# UltiMem64_Color_CPLD.net
KiCad netlist of a schematic drawn in EAGLE
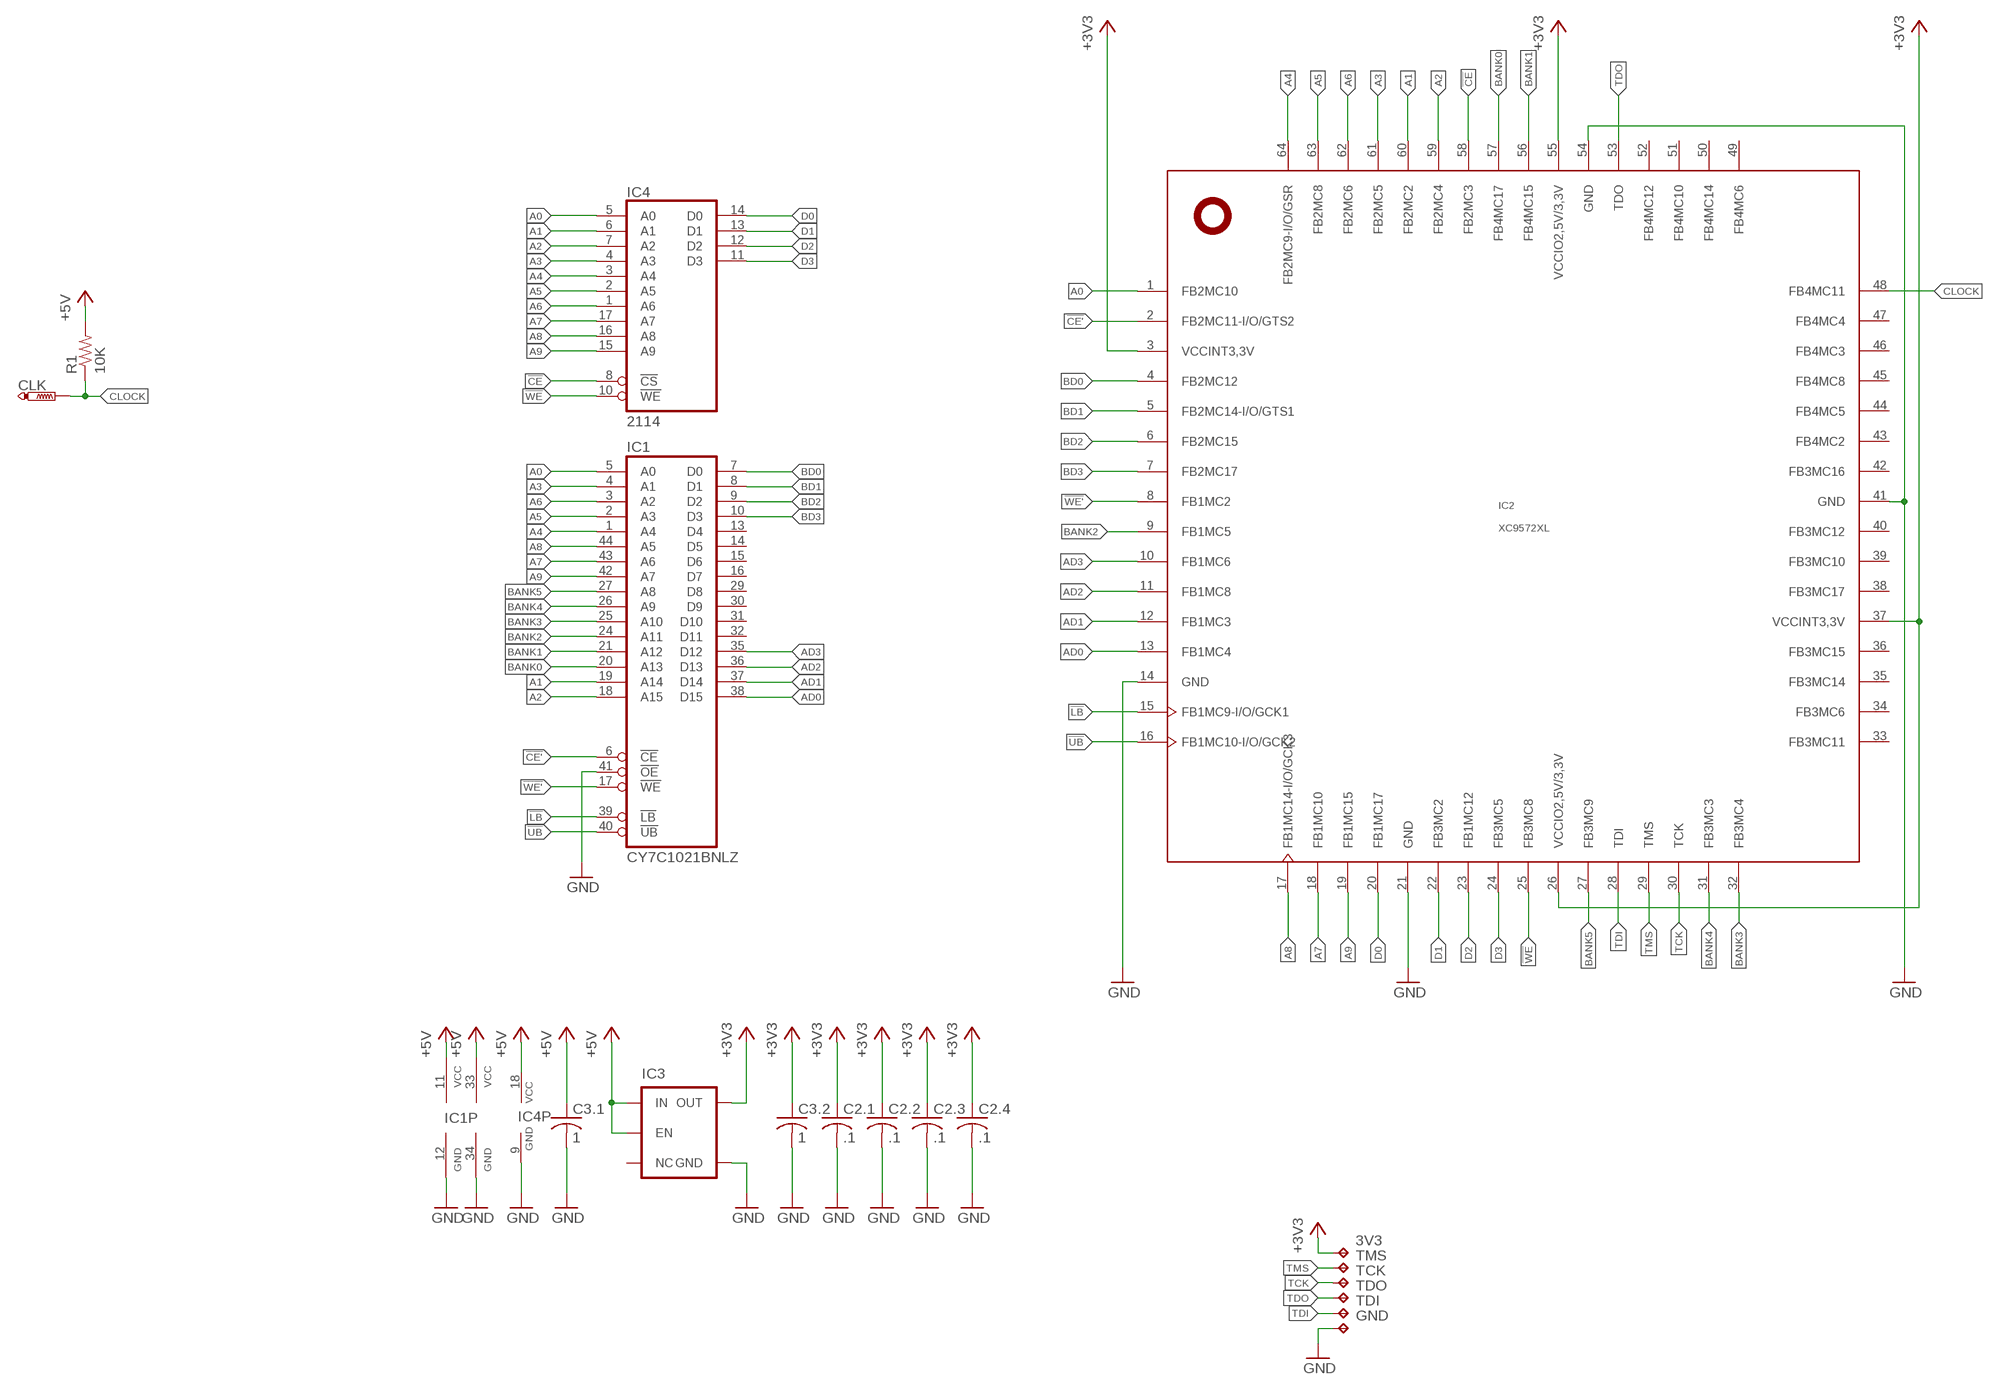
[diagram p0: schematic, sheet 1]

(export (version "E")
  (design (tool "Eeschema 10.0.6"))
  (components
    (comp (ref "3V3")
      (value "TPTP09R")
      (footprint "eagle-import:TP09R")
      (libsource (lib "eagle-import") (part "TPTP09R"))
    )
    (comp (ref "C2.1")
      (value ".1")
      (footprint "eagle-import:C0402")
      (libsource (lib "eagle-import") (part "C-USC0402"))
    )
    (comp (ref "C2.2")
      (value ".1")
      (footprint "eagle-import:C0402")
      (libsource (lib "eagle-import") (part "C-USC0402"))
    )
    (comp (ref "C2.3")
      (value ".1")
      (footprint "eagle-import:C0402")
      (libsource (lib "eagle-import") (part "C-USC0402"))
    )
    (comp (ref "C2.4")
      (value ".1")
      (footprint "eagle-import:C0402")
      (libsource (lib "eagle-import") (part "C-USC0402"))
    )
    (comp (ref "C3.1")
      (value "1")
      (footprint "eagle-import:C0402")
      (libsource (lib "eagle-import") (part "C-USC0402"))
    )
    (comp (ref "C3.2")
      (value "1")
      (footprint "eagle-import:C0402")
      (libsource (lib "eagle-import") (part "C-USC0402"))
    )
    (comp (ref "CLK")
      (value "PTR1PAD1-13")
      (footprint "eagle-import:P1-13")
      (libsource (lib "eagle-import") (part "PTR1PAD1-13"))
    )
    (comp (ref "GND")
      (value "TPTP09R")
      (footprint "eagle-import:TP09R")
      (libsource (lib "eagle-import") (part "TPTP09R"))
    )
    (comp (ref "IC1")
      (value "CY7C1021BNLZ")
      (footprint "eagle-import:TSOP44-II")
      (libsource (lib "eagle-import") (part "CY7C1021BNLZ"))
    )
    (comp (ref "IC2")
      (value "XC9572XL")
      (footprint "eagle-import:VQFP64")
      (libsource (lib "eagle-import") (part "XC9572XLVQG64"))
    )
    (comp (ref "IC3")
      (value "V_REG_TPS76433SOT23-5")
      (footprint "eagle-import:SOT23-5")
      (libsource (lib "eagle-import") (part "V_REG_TPS76433SOT23-5"))
    )
    (comp (ref "IC4")
      (value "2114")
      (footprint "eagle-import:DIL18-SMD-REVERSE")
      (libsource (lib "eagle-import") (part "2114-S"))
    )
    (comp (ref "R1")
      (value "10K")
      (footprint "eagle-import:R0402")
      (libsource (lib "eagle-import") (part "R-US_R0402"))
    )
    (comp (ref "TCK")
      (value "TPTP09R")
      (footprint "eagle-import:TP09R")
      (libsource (lib "eagle-import") (part "TPTP09R"))
    )
    (comp (ref "TDI")
      (value "TPTP09R")
      (footprint "eagle-import:TP09R")
      (libsource (lib "eagle-import") (part "TPTP09R"))
    )
    (comp (ref "TDO")
      (value "TPTP09R")
      (footprint "eagle-import:TP09R")
      (libsource (lib "eagle-import") (part "TPTP09R"))
    )
    (comp (ref "TMS")
      (value "TPTP09R")
      (footprint "eagle-import:TP09R")
      (libsource (lib "eagle-import") (part "TPTP09R"))
    )
  )
  (nets
    (net (code "1") (name "+3V3") (class "Default")
      (node (ref "3V3") (pin "TP") (pinfunction "TP_TP") (pintype "input"))
      (node (ref "C2.1") (pin "1") (pinfunction "1_1") (pintype "passive"))
      (node (ref "C2.2") (pin "1") (pinfunction "1_1") (pintype "passive"))
      (node (ref "C2.3") (pin "1") (pinfunction "1_1") (pintype "passive"))
      (node (ref "C2.4") (pin "1") (pinfunction "1_1") (pintype "passive"))
      (node (ref "C3.2") (pin "1") (pinfunction "1_1") (pintype "passive"))
      (node (ref "IC2") (pin "26") (pinfunction "VCCIO2,5V/3,3V_26") (pintype "power_in"))
      (node (ref "IC2") (pin "3") (pinfunction "VCCINT3,3V_3") (pintype "power_in"))
      (node (ref "IC2") (pin "37") (pinfunction "VCCINT3,3V_37") (pintype "power_in"))
      (node (ref "IC2") (pin "55") (pinfunction "VCCIO2,5V/3,3V_55") (pintype "power_in"))
      (node (ref "IC3") (pin "5") (pinfunction "OUT_5") (pintype "passive"))
    )
    (net (code "2") (name "+5V") (class "Default")
      (node (ref "C3.1") (pin "1") (pinfunction "1_1") (pintype "passive"))
      (node (ref "IC1") (pin "11") (pinfunction "VCC_11") (pintype "power_in"))
      (node (ref "IC1") (pin "33") (pinfunction "VCC_33") (pintype "power_in"))
      (node (ref "IC3") (pin "1") (pinfunction "IN_1") (pintype "input"))
      (node (ref "IC3") (pin "3") (pinfunction "EN_3") (pintype "input"))
      (node (ref "IC4") (pin "18") (pinfunction "VCC_18") (pintype "power_in"))
      (node (ref "R1") (pin "2") (pinfunction "2_2") (pintype "passive"))
    )
    (net (code "3") (name "/~{CE'}") (class "Default")
      (node (ref "IC1") (pin "6") (pinfunction "~{CE}_6") (pintype "input"))
      (node (ref "IC2") (pin "2") (pinfunction "FB2MC11-I/O/GTS2_2") (pintype "bidirectional"))
    )
    (net (code "4") (name "/~{CE}") (class "Default")
      (node (ref "IC2") (pin "58") (pinfunction "FB2MC3_58") (pintype "bidirectional"))
      (node (ref "IC4") (pin "8") (pinfunction "~{CS}_8") (pintype "input"))
    )
    (net (code "5") (name "/~{LB}") (class "Default")
      (node (ref "IC1") (pin "39") (pinfunction "~{LB}_39") (pintype "input"))
      (node (ref "IC2") (pin "15") (pinfunction "FB1MC9-I/O/GCK1_15") (pintype "bidirectional"))
    )
    (net (code "6") (name "/~{UB}") (class "Default")
      (node (ref "IC1") (pin "40") (pinfunction "~{UB}_40") (pintype "input"))
      (node (ref "IC2") (pin "16") (pinfunction "FB1MC10-I/O/GCK2_16") (pintype "bidirectional"))
    )
    (net (code "7") (name "/~{WE'}") (class "Default")
      (node (ref "IC1") (pin "17") (pinfunction "~{WE}_17") (pintype "input"))
      (node (ref "IC2") (pin "8") (pinfunction "FB1MC2_8") (pintype "bidirectional"))
    )
    (net (code "8") (name "/~{WE}") (class "Default")
      (node (ref "IC2") (pin "25") (pinfunction "FB3MC8_25") (pintype "bidirectional"))
      (node (ref "IC4") (pin "10") (pinfunction "~{WE}_10") (pintype "input"))
    )
    (net (code "9") (name "A0") (class "Default")
      (node (ref "IC1") (pin "5") (pinfunction "A0_5") (pintype "input"))
      (node (ref "IC2") (pin "1") (pinfunction "FB2MC10_1") (pintype "bidirectional"))
      (node (ref "IC4") (pin "5") (pinfunction "A0_5") (pintype "input"))
    )
    (net (code "10") (name "A1") (class "Default")
      (node (ref "IC1") (pin "19") (pinfunction "A14_19") (pintype "input"))
      (node (ref "IC2") (pin "60") (pinfunction "FB2MC2_60") (pintype "bidirectional"))
      (node (ref "IC4") (pin "6") (pinfunction "A1_6") (pintype "input"))
    )
    (net (code "11") (name "A2") (class "Default")
      (node (ref "IC1") (pin "18") (pinfunction "A15_18") (pintype "input"))
      (node (ref "IC2") (pin "59") (pinfunction "FB2MC4_59") (pintype "bidirectional"))
      (node (ref "IC4") (pin "7") (pinfunction "A2_7") (pintype "input"))
    )
    (net (code "12") (name "A3") (class "Default")
      (node (ref "IC1") (pin "4") (pinfunction "A1_4") (pintype "input"))
      (node (ref "IC2") (pin "61") (pinfunction "FB2MC5_61") (pintype "bidirectional"))
      (node (ref "IC4") (pin "4") (pinfunction "A3_4") (pintype "input"))
    )
    (net (code "13") (name "A4") (class "Default")
      (node (ref "IC1") (pin "1") (pinfunction "A4_1") (pintype "input"))
      (node (ref "IC2") (pin "64") (pinfunction "FB2MC9-I/O/GSR_64") (pintype "bidirectional"))
      (node (ref "IC4") (pin "3") (pinfunction "A4_3") (pintype "input"))
    )
    (net (code "14") (name "A5") (class "Default")
      (node (ref "IC1") (pin "2") (pinfunction "A3_2") (pintype "input"))
      (node (ref "IC2") (pin "63") (pinfunction "FB2MC8_63") (pintype "bidirectional"))
      (node (ref "IC4") (pin "2") (pinfunction "A5_2") (pintype "input"))
    )
    (net (code "15") (name "A6") (class "Default")
      (node (ref "IC1") (pin "3") (pinfunction "A2_3") (pintype "input"))
      (node (ref "IC2") (pin "62") (pinfunction "FB2MC6_62") (pintype "bidirectional"))
      (node (ref "IC4") (pin "1") (pinfunction "A6_1") (pintype "input"))
    )
    (net (code "16") (name "A7") (class "Default")
      (node (ref "IC1") (pin "43") (pinfunction "A6_43") (pintype "input"))
      (node (ref "IC2") (pin "18") (pinfunction "FB1MC10_18") (pintype "bidirectional"))
      (node (ref "IC4") (pin "17") (pinfunction "A7_17") (pintype "input"))
    )
    (net (code "17") (name "A8") (class "Default")
      (node (ref "IC1") (pin "44") (pinfunction "A5_44") (pintype "input"))
      (node (ref "IC2") (pin "17") (pinfunction "FB1MC14-I/O/GCK3_17") (pintype "bidirectional"))
      (node (ref "IC4") (pin "16") (pinfunction "A8_16") (pintype "input"))
    )
    (net (code "18") (name "A9") (class "Default")
      (node (ref "IC1") (pin "42") (pinfunction "A7_42") (pintype "input"))
      (node (ref "IC2") (pin "19") (pinfunction "FB1MC15_19") (pintype "bidirectional"))
      (node (ref "IC4") (pin "15") (pinfunction "A9_15") (pintype "input"))
    )
    (net (code "19") (name "AD0") (class "Default")
      (node (ref "IC1") (pin "38") (pinfunction "D15_38") (pintype "bidirectional"))
      (node (ref "IC2") (pin "13") (pinfunction "FB1MC4_13") (pintype "bidirectional"))
    )
    (net (code "20") (name "AD1") (class "Default")
      (node (ref "IC1") (pin "37") (pinfunction "D14_37") (pintype "bidirectional"))
      (node (ref "IC2") (pin "12") (pinfunction "FB1MC3_12") (pintype "bidirectional"))
    )
    (net (code "21") (name "AD2") (class "Default")
      (node (ref "IC1") (pin "36") (pinfunction "D13_36") (pintype "bidirectional"))
      (node (ref "IC2") (pin "11") (pinfunction "FB1MC8_11") (pintype "bidirectional"))
    )
    (net (code "22") (name "AD3") (class "Default")
      (node (ref "IC1") (pin "35") (pinfunction "D12_35") (pintype "bidirectional"))
      (node (ref "IC2") (pin "10") (pinfunction "FB1MC6_10") (pintype "bidirectional"))
    )
    (net (code "23") (name "BANK0") (class "Default")
      (node (ref "IC1") (pin "20") (pinfunction "A13_20") (pintype "input"))
      (node (ref "IC2") (pin "57") (pinfunction "FB4MC17_57") (pintype "bidirectional"))
    )
    (net (code "24") (name "BANK1") (class "Default")
      (node (ref "IC1") (pin "21") (pinfunction "A12_21") (pintype "input"))
      (node (ref "IC2") (pin "56") (pinfunction "FB4MC15_56") (pintype "bidirectional"))
    )
    (net (code "25") (name "BANK2") (class "Default")
      (node (ref "IC1") (pin "24") (pinfunction "A11_24") (pintype "input"))
      (node (ref "IC2") (pin "9") (pinfunction "FB1MC5_9") (pintype "bidirectional"))
    )
    (net (code "26") (name "BANK3") (class "Default")
      (node (ref "IC1") (pin "25") (pinfunction "A10_25") (pintype "input"))
      (node (ref "IC2") (pin "32") (pinfunction "FB3MC4_32") (pintype "bidirectional"))
    )
    (net (code "27") (name "BANK4") (class "Default")
      (node (ref "IC1") (pin "26") (pinfunction "A9_26") (pintype "input"))
      (node (ref "IC2") (pin "31") (pinfunction "FB3MC3_31") (pintype "bidirectional"))
    )
    (net (code "28") (name "BANK5") (class "Default")
      (node (ref "IC1") (pin "27") (pinfunction "A8_27") (pintype "input"))
      (node (ref "IC2") (pin "27") (pinfunction "FB3MC9_27") (pintype "bidirectional"))
    )
    (net (code "29") (name "BD0") (class "Default")
      (node (ref "IC1") (pin "7") (pinfunction "D0_7") (pintype "bidirectional"))
      (node (ref "IC2") (pin "4") (pinfunction "FB2MC12_4") (pintype "bidirectional"))
    )
    (net (code "30") (name "BD1") (class "Default")
      (node (ref "IC1") (pin "8") (pinfunction "D1_8") (pintype "bidirectional"))
      (node (ref "IC2") (pin "5") (pinfunction "FB2MC14-I/O/GTS1_5") (pintype "bidirectional"))
    )
    (net (code "31") (name "BD2") (class "Default")
      (node (ref "IC1") (pin "9") (pinfunction "D2_9") (pintype "bidirectional"))
      (node (ref "IC2") (pin "6") (pinfunction "FB2MC15_6") (pintype "bidirectional"))
    )
    (net (code "32") (name "BD3") (class "Default")
      (node (ref "IC1") (pin "10") (pinfunction "D3_10") (pintype "bidirectional"))
      (node (ref "IC2") (pin "7") (pinfunction "FB2MC17_7") (pintype "bidirectional"))
    )
    (net (code "33") (name "CLOCK") (class "Default")
      (node (ref "CLK") (pin "TP") (pinfunction "TP_TP") (pintype "input"))
      (node (ref "IC2") (pin "48") (pinfunction "FB4MC11_48") (pintype "bidirectional"))
      (node (ref "R1") (pin "1") (pinfunction "1_1") (pintype "passive"))
    )
    (net (code "34") (name "D0") (class "Default")
      (node (ref "IC2") (pin "20") (pinfunction "FB1MC17_20") (pintype "bidirectional"))
      (node (ref "IC4") (pin "14") (pinfunction "D0_14") (pintype "bidirectional"))
    )
    (net (code "35") (name "D1") (class "Default")
      (node (ref "IC2") (pin "22") (pinfunction "FB3MC2_22") (pintype "bidirectional"))
      (node (ref "IC4") (pin "13") (pinfunction "D1_13") (pintype "bidirectional"))
    )
    (net (code "36") (name "D2") (class "Default")
      (node (ref "IC2") (pin "23") (pinfunction "FB1MC12_23") (pintype "bidirectional"))
      (node (ref "IC4") (pin "12") (pinfunction "D2_12") (pintype "bidirectional"))
    )
    (net (code "37") (name "D3") (class "Default")
      (node (ref "IC2") (pin "24") (pinfunction "FB3MC5_24") (pintype "bidirectional"))
      (node (ref "IC4") (pin "11") (pinfunction "D3_11") (pintype "bidirectional"))
    )
    (net (code "38") (name "GND") (class "Default")
      (node (ref "C2.1") (pin "2") (pinfunction "2_2") (pintype "passive"))
      (node (ref "C2.2") (pin "2") (pinfunction "2_2") (pintype "passive"))
      (node (ref "C2.3") (pin "2") (pinfunction "2_2") (pintype "passive"))
      (node (ref "C2.4") (pin "2") (pinfunction "2_2") (pintype "passive"))
      (node (ref "C3.1") (pin "2") (pinfunction "2_2") (pintype "passive"))
      (node (ref "C3.2") (pin "2") (pinfunction "2_2") (pintype "passive"))
      (node (ref "GND") (pin "TP") (pinfunction "TP_TP") (pintype "input"))
      (node (ref "IC1") (pin "12") (pinfunction "GND_12") (pintype "power_in"))
      (node (ref "IC1") (pin "34") (pinfunction "GND_34") (pintype "power_in"))
      (node (ref "IC1") (pin "41") (pinfunction "~{OE}_41") (pintype "input"))
      (node (ref "IC2") (pin "14") (pinfunction "GND_14") (pintype "power_in"))
      (node (ref "IC2") (pin "21") (pinfunction "GND_21") (pintype "power_in"))
      (node (ref "IC2") (pin "41") (pinfunction "GND_41") (pintype "power_in"))
      (node (ref "IC2") (pin "54") (pinfunction "GND_54") (pintype "power_in"))
      (node (ref "IC3") (pin "2") (pinfunction "GND_2") (pintype "input"))
      (node (ref "IC4") (pin "9") (pinfunction "GND_9") (pintype "power_in"))
    )
    (net (code "39") (name "TCK") (class "Default")
      (node (ref "IC2") (pin "30") (pinfunction "TCK_30") (pintype "bidirectional"))
      (node (ref "TCK") (pin "TP") (pinfunction "TP_TP") (pintype "input"))
    )
    (net (code "40") (name "TDI") (class "Default")
      (node (ref "IC2") (pin "28") (pinfunction "TDI_28") (pintype "bidirectional"))
      (node (ref "TDI") (pin "TP") (pinfunction "TP_TP") (pintype "input"))
    )
    (net (code "41") (name "TDO") (class "Default")
      (node (ref "IC2") (pin "53") (pinfunction "TDO_53") (pintype "bidirectional"))
      (node (ref "TDO") (pin "TP") (pinfunction "TP_TP") (pintype "input"))
    )
    (net (code "42") (name "TMS") (class "Default")
      (node (ref "IC2") (pin "29") (pinfunction "TMS_29") (pintype "bidirectional"))
      (node (ref "TMS") (pin "TP") (pinfunction "TP_TP") (pintype "input"))
    )
    (net (code "43") (name "unconnected-(IC1A-D4-Pad13)") (class "Default")
      (node (ref "IC1") (pin "13") (pinfunction "D4_13") (pintype "bidirectional"))
    )
    (net (code "44") (name "unconnected-(IC1A-D5-Pad14)") (class "Default")
      (node (ref "IC1") (pin "14") (pinfunction "D5_14") (pintype "bidirectional"))
    )
    (net (code "45") (name "unconnected-(IC1A-D6-Pad15)") (class "Default")
      (node (ref "IC1") (pin "15") (pinfunction "D6_15") (pintype "bidirectional"))
    )
    (net (code "46") (name "unconnected-(IC1A-D7-Pad16)") (class "Default")
      (node (ref "IC1") (pin "16") (pinfunction "D7_16") (pintype "bidirectional"))
    )
    (net (code "47") (name "unconnected-(IC1A-D8-Pad29)") (class "Default")
      (node (ref "IC1") (pin "29") (pinfunction "D8_29") (pintype "bidirectional"))
    )
    (net (code "48") (name "unconnected-(IC1A-D9-Pad30)") (class "Default")
      (node (ref "IC1") (pin "30") (pinfunction "D9_30") (pintype "bidirectional"))
    )
    (net (code "49") (name "unconnected-(IC1A-D10-Pad31)") (class "Default")
      (node (ref "IC1") (pin "31") (pinfunction "D10_31") (pintype "bidirectional"))
    )
    (net (code "50") (name "unconnected-(IC1A-D11-Pad32)") (class "Default")
      (node (ref "IC1") (pin "32") (pinfunction "D11_32") (pintype "bidirectional"))
    )
    (net (code "51") (name "unconnected-(IC2-FB3MC6-Pad34)") (class "Default")
      (node (ref "IC2") (pin "34") (pinfunction "FB3MC6_34") (pintype "bidirectional"))
    )
    (net (code "52") (name "unconnected-(IC2-FB3MC10-Pad39)") (class "Default")
      (node (ref "IC2") (pin "39") (pinfunction "FB3MC10_39") (pintype "bidirectional"))
    )
    (net (code "53") (name "unconnected-(IC2-FB3MC11-Pad33)") (class "Default")
      (node (ref "IC2") (pin "33") (pinfunction "FB3MC11_33") (pintype "bidirectional"))
    )
    (net (code "54") (name "unconnected-(IC2-FB3MC12-Pad40)") (class "Default")
      (node (ref "IC2") (pin "40") (pinfunction "FB3MC12_40") (pintype "bidirectional"))
    )
    (net (code "55") (name "unconnected-(IC2-FB3MC14-Pad35)") (class "Default")
      (node (ref "IC2") (pin "35") (pinfunction "FB3MC14_35") (pintype "bidirectional"))
    )
    (net (code "56") (name "unconnected-(IC2-FB3MC15-Pad36)") (class "Default")
      (node (ref "IC2") (pin "36") (pinfunction "FB3MC15_36") (pintype "bidirectional"))
    )
    (net (code "57") (name "unconnected-(IC2-FB3MC16-Pad42)") (class "Default")
      (node (ref "IC2") (pin "42") (pinfunction "FB3MC16_42") (pintype "bidirectional"))
    )
    (net (code "58") (name "unconnected-(IC2-FB3MC17-Pad38)") (class "Default")
      (node (ref "IC2") (pin "38") (pinfunction "FB3MC17_38") (pintype "bidirectional"))
    )
    (net (code "59") (name "unconnected-(IC2-FB4MC2-Pad43)") (class "Default")
      (node (ref "IC2") (pin "43") (pinfunction "FB4MC2_43") (pintype "bidirectional"))
    )
    (net (code "60") (name "unconnected-(IC2-FB4MC3-Pad46)") (class "Default")
      (node (ref "IC2") (pin "46") (pinfunction "FB4MC3_46") (pintype "bidirectional"))
    )
    (net (code "61") (name "unconnected-(IC2-FB4MC4-Pad47)") (class "Default")
      (node (ref "IC2") (pin "47") (pinfunction "FB4MC4_47") (pintype "bidirectional"))
    )
    (net (code "62") (name "unconnected-(IC2-FB4MC5-Pad44)") (class "Default")
      (node (ref "IC2") (pin "44") (pinfunction "FB4MC5_44") (pintype "bidirectional"))
    )
    (net (code "63") (name "unconnected-(IC2-FB4MC6-Pad49)") (class "Default")
      (node (ref "IC2") (pin "49") (pinfunction "FB4MC6_49") (pintype "bidirectional"))
    )
    (net (code "64") (name "unconnected-(IC2-FB4MC8-Pad45)") (class "Default")
      (node (ref "IC2") (pin "45") (pinfunction "FB4MC8_45") (pintype "bidirectional"))
    )
    (net (code "65") (name "unconnected-(IC2-FB4MC10-Pad51)") (class "Default")
      (node (ref "IC2") (pin "51") (pinfunction "FB4MC10_51") (pintype "bidirectional"))
    )
    (net (code "66") (name "unconnected-(IC2-FB4MC12-Pad52)") (class "Default")
      (node (ref "IC2") (pin "52") (pinfunction "FB4MC12_52") (pintype "bidirectional"))
    )
    (net (code "67") (name "unconnected-(IC2-FB4MC14-Pad50)") (class "Default")
      (node (ref "IC2") (pin "50") (pinfunction "FB4MC14_50") (pintype "bidirectional"))
    )
    (net (code "68") (name "unconnected-(IC3-NC-Pad4)") (class "Default")
      (node (ref "IC3") (pin "4") (pinfunction "NC_4") (pintype "input"))
    )
  )
)
